# iSEB_SoundRecognition_2503.net
KiCad netlist of a schematic drawn in Altium Designer
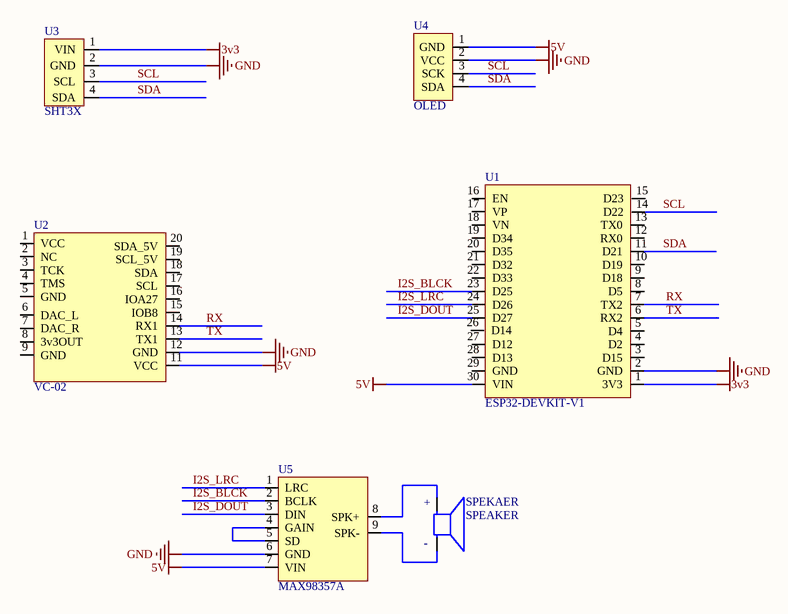
[diagram p0: iSEB_SoundRecognition_2503.SchDoc]

(export (version "E")
  (design (tool "Eeschema 10.0.6"))
  (components
    (comp (ref "SPEKAER")
      (value "SPEAKER")
      (footprint "SPKR_AST-03208MR-R")
      (fields (field (name "MP") "AST-03208MR-R"))
      (libsource (lib "BingRan_2019") (part "SPEAKER"))
    )
    (comp (ref "U1")
      (value "ESP32-DEVKIT-V1")
      (footprint "MODULE_ESP32_DEVKIT_V1")
      (fields (field (name "MF") "Do it"))
      (libsource (lib "BingRan_2019") (part "ESP32-DEVKIT-V1_NO_SOCKET"))
    )
    (comp (ref "U2") (value "VC-02") (libsource (lib "BingRan_2019") (part "VC-02")))
    (comp (ref "U3") (value "SHT3X") (libsource (lib "BingRan_2019") (part "SHT3X")))
    (comp (ref "U4") (value "OLED") (libsource (lib "BingRan_2019") (part "OLED")))
    (comp (ref "U5") (value "MAX98357A") (libsource (lib "BingRan_2019") (part "MAX98357A")))
  )
  (nets
    (net (code "1") (name "/I2S_BLCK") (class "Default")
      (node (ref "U1") (pin "23") (pinfunction "D25_23") (pintype "passive"))
      (node (ref "U5") (pin "2") (pinfunction "BCLK_2") (pintype "passive"))
    )
    (net (code "2") (name "/I2S_DOUT") (class "Default")
      (node (ref "U1") (pin "25") (pinfunction "D27_25") (pintype "passive"))
      (node (ref "U5") (pin "3") (pinfunction "DIN_3") (pintype "passive"))
    )
    (net (code "3") (name "/I2S_LRC") (class "Default")
      (node (ref "U1") (pin "24") (pinfunction "D26_24") (pintype "passive"))
      (node (ref "U5") (pin "1") (pinfunction "LRC_1") (pintype "passive"))
    )
    (net (code "4") (name "/RX") (class "Default")
      (node (ref "U1") (pin "7") (pinfunction "TX2_7") (pintype "passive"))
      (node (ref "U2") (pin "14") (pinfunction "RX1_14") (pintype "passive"))
    )
    (net (code "5") (name "/SCL") (class "Default")
      (node (ref "U1") (pin "14") (pinfunction "D22_14") (pintype "passive"))
      (node (ref "U3") (pin "3") (pinfunction "SCL_3") (pintype "passive"))
      (node (ref "U4") (pin "3") (pinfunction "SCK_3") (pintype "passive"))
    )
    (net (code "6") (name "/SDA") (class "Default")
      (node (ref "U1") (pin "11") (pinfunction "D21_11") (pintype "passive"))
      (node (ref "U3") (pin "4") (pinfunction "SDA_4") (pintype "passive"))
      (node (ref "U4") (pin "4") (pinfunction "SDA_4") (pintype "passive"))
    )
    (net (code "7") (name "/TX") (class "Default")
      (node (ref "U1") (pin "6") (pinfunction "RX2_6") (pintype "passive"))
      (node (ref "U2") (pin "13") (pinfunction "TX1_13") (pintype "passive"))
    )
    (net (code "8") (name "3v3") (class "Default")
      (node (ref "U1") (pin "1") (pinfunction "3V3_1") (pintype "passive"))
      (node (ref "U3") (pin "1") (pinfunction "VIN_1") (pintype "passive"))
    )
    (net (code "9") (name "5V") (class "Default")
      (node (ref "U1") (pin "30") (pinfunction "VIN_30") (pintype "passive"))
      (node (ref "U2") (pin "11") (pinfunction "VCC_11") (pintype "passive"))
      (node (ref "U4") (pin "1") (pinfunction "GND_1") (pintype "passive"))
      (node (ref "U5") (pin "7") (pinfunction "VIN_7") (pintype "passive"))
    )
    (net (code "10") (name "GND") (class "Default")
      (node (ref "U1") (pin "2") (pinfunction "GND_2") (pintype "passive"))
      (node (ref "U2") (pin "12") (pinfunction "GND_12") (pintype "passive"))
      (node (ref "U3") (pin "2") (pinfunction "GND_2") (pintype "passive"))
      (node (ref "U4") (pin "2") (pinfunction "VCC_2") (pintype "passive"))
      (node (ref "U5") (pin "6") (pinfunction "GND_6") (pintype "passive"))
    )
    (net (code "11") (name "Net-(SPEKAER-NEG)") (class "Default")
      (node (ref "SPEKAER") (pin "N") (pinfunction "NEG_N") (pintype "passive"))
      (node (ref "U5") (pin "9") (pinfunction "SPK-_9") (pintype "passive"))
    )
    (net (code "12") (name "Net-(SPEKAER-POS)") (class "Default")
      (node (ref "SPEKAER") (pin "P") (pinfunction "POS_P") (pintype "passive"))
      (node (ref "U5") (pin "8") (pinfunction "SPK+_8") (pintype "passive"))
    )
    (net (code "13") (name "Net-(U5-GAIN)") (class "Default")
      (node (ref "U5") (pin "4") (pinfunction "GAIN_4") (pintype "passive"))
      (node (ref "U5") (pin "5") (pinfunction "SD_5") (pintype "passive"))
    )
    (net (code "14") (name "unconnected-(U1-D2-Pad4)") (class "Default")
      (node (ref "U1") (pin "4") (pinfunction "D2_4") (pintype "passive"))
    )
    (net (code "15") (name "unconnected-(U1-D4-Pad5)") (class "Default")
      (node (ref "U1") (pin "5") (pinfunction "D4_5") (pintype "passive"))
    )
    (net (code "16") (name "unconnected-(U1-D5-Pad8)") (class "Default")
      (node (ref "U1") (pin "8") (pinfunction "D5_8") (pintype "passive"))
    )
    (net (code "17") (name "unconnected-(U1-D12-Pad27)") (class "Default")
      (node (ref "U1") (pin "27") (pinfunction "D12_27") (pintype "passive"))
    )
    (net (code "18") (name "unconnected-(U1-D13-Pad28)") (class "Default")
      (node (ref "U1") (pin "28") (pinfunction "D13_28") (pintype "passive"))
    )
    (net (code "19") (name "unconnected-(U1-D14-Pad26)") (class "Default")
      (node (ref "U1") (pin "26") (pinfunction "D14_26") (pintype "passive"))
    )
    (net (code "20") (name "unconnected-(U1-D15-Pad3)") (class "Default")
      (node (ref "U1") (pin "3") (pinfunction "D15_3") (pintype "passive"))
    )
    (net (code "21") (name "unconnected-(U1-D18-Pad9)") (class "Default")
      (node (ref "U1") (pin "9") (pinfunction "D18_9") (pintype "passive"))
    )
    (net (code "22") (name "unconnected-(U1-D19-Pad10)") (class "Default")
      (node (ref "U1") (pin "10") (pinfunction "D19_10") (pintype "passive"))
    )
    (net (code "23") (name "unconnected-(U1-D23-Pad15)") (class "Default")
      (node (ref "U1") (pin "15") (pinfunction "D23_15") (pintype "passive"))
    )
    (net (code "24") (name "unconnected-(U1-D32-Pad21)") (class "Default")
      (node (ref "U1") (pin "21") (pinfunction "D32_21") (pintype "passive"))
    )
    (net (code "25") (name "unconnected-(U1-D33-Pad22)") (class "Default")
      (node (ref "U1") (pin "22") (pinfunction "D33_22") (pintype "passive"))
    )
    (net (code "26") (name "unconnected-(U1-D34-Pad19)") (class "Default")
      (node (ref "U1") (pin "19") (pinfunction "D34_19") (pintype "passive"))
    )
    (net (code "27") (name "unconnected-(U1-D35-Pad20)") (class "Default")
      (node (ref "U1") (pin "20") (pinfunction "D35_20") (pintype "passive"))
    )
    (net (code "28") (name "unconnected-(U1-EN-Pad16)") (class "Default")
      (node (ref "U1") (pin "16") (pinfunction "EN_16") (pintype "passive"))
    )
    (net (code "29") (name "unconnected-(U1-GND-Pad29)") (class "Default")
      (node (ref "U1") (pin "29") (pinfunction "GND_29") (pintype "passive"))
    )
    (net (code "30") (name "unconnected-(U1-RX0-Pad12)") (class "Default")
      (node (ref "U1") (pin "12") (pinfunction "RX0_12") (pintype "passive"))
    )
    (net (code "31") (name "unconnected-(U1-TX0-Pad13)") (class "Default")
      (node (ref "U1") (pin "13") (pinfunction "TX0_13") (pintype "passive"))
    )
    (net (code "32") (name "unconnected-(U1-VN-Pad18)") (class "Default")
      (node (ref "U1") (pin "18") (pinfunction "VN_18") (pintype "passive"))
    )
    (net (code "33") (name "unconnected-(U1-VP-Pad17)") (class "Default")
      (node (ref "U1") (pin "17") (pinfunction "VP_17") (pintype "passive"))
    )
    (net (code "34") (name "unconnected-(U2-3v3OUT-Pad8)") (class "Default")
      (node (ref "U2") (pin "8") (pinfunction "3v3OUT_8") (pintype "passive"))
    )
    (net (code "35") (name "unconnected-(U2-DAC_L-Pad6)") (class "Default")
      (node (ref "U2") (pin "6") (pinfunction "DAC_L_6") (pintype "passive"))
    )
    (net (code "36") (name "unconnected-(U2-DAC_R-Pad7)") (class "Default")
      (node (ref "U2") (pin "7") (pinfunction "DAC_R_7") (pintype "passive"))
    )
    (net (code "37") (name "unconnected-(U2-GND-Pad5)") (class "Default")
      (node (ref "U2") (pin "5") (pinfunction "GND_5") (pintype "passive"))
    )
    (net (code "38") (name "unconnected-(U2-GND-Pad9)") (class "Default")
      (node (ref "U2") (pin "9") (pinfunction "GND_9") (pintype "passive"))
    )
    (net (code "39") (name "unconnected-(U2-IOA27-Pad16)") (class "Default")
      (node (ref "U2") (pin "16") (pinfunction "IOA27_16") (pintype "passive"))
    )
    (net (code "40") (name "unconnected-(U2-IOB8-Pad15)") (class "Default")
      (node (ref "U2") (pin "15") (pinfunction "IOB8_15") (pintype "passive"))
    )
    (net (code "41") (name "unconnected-(U2-NC-Pad2)") (class "Default")
      (node (ref "U2") (pin "2") (pinfunction "NC_2") (pintype "passive"))
    )
    (net (code "42") (name "unconnected-(U2-SCL-Pad17)") (class "Default")
      (node (ref "U2") (pin "17") (pinfunction "SCL_17") (pintype "passive"))
    )
    (net (code "43") (name "unconnected-(U2-SCL_5V-Pad19)") (class "Default")
      (node (ref "U2") (pin "19") (pinfunction "SCL_5V_19") (pintype "passive"))
    )
    (net (code "44") (name "unconnected-(U2-SDA-Pad18)") (class "Default")
      (node (ref "U2") (pin "18") (pinfunction "SDA_18") (pintype "passive"))
    )
    (net (code "45") (name "unconnected-(U2-SDA_5V-Pad20)") (class "Default")
      (node (ref "U2") (pin "20") (pinfunction "SDA_5V_20") (pintype "passive"))
    )
    (net (code "46") (name "unconnected-(U2-TCK-Pad3)") (class "Default")
      (node (ref "U2") (pin "3") (pinfunction "TCK_3") (pintype "passive"))
    )
    (net (code "47") (name "unconnected-(U2-TMS-Pad4)") (class "Default")
      (node (ref "U2") (pin "4") (pinfunction "TMS_4") (pintype "passive"))
    )
    (net (code "48") (name "unconnected-(U2-VCC-Pad1)") (class "Default")
      (node (ref "U2") (pin "1") (pinfunction "VCC_1") (pintype "passive"))
    )
  )
)
